# design.net
KiCad netlist of a schematic drawn in Altium Designer
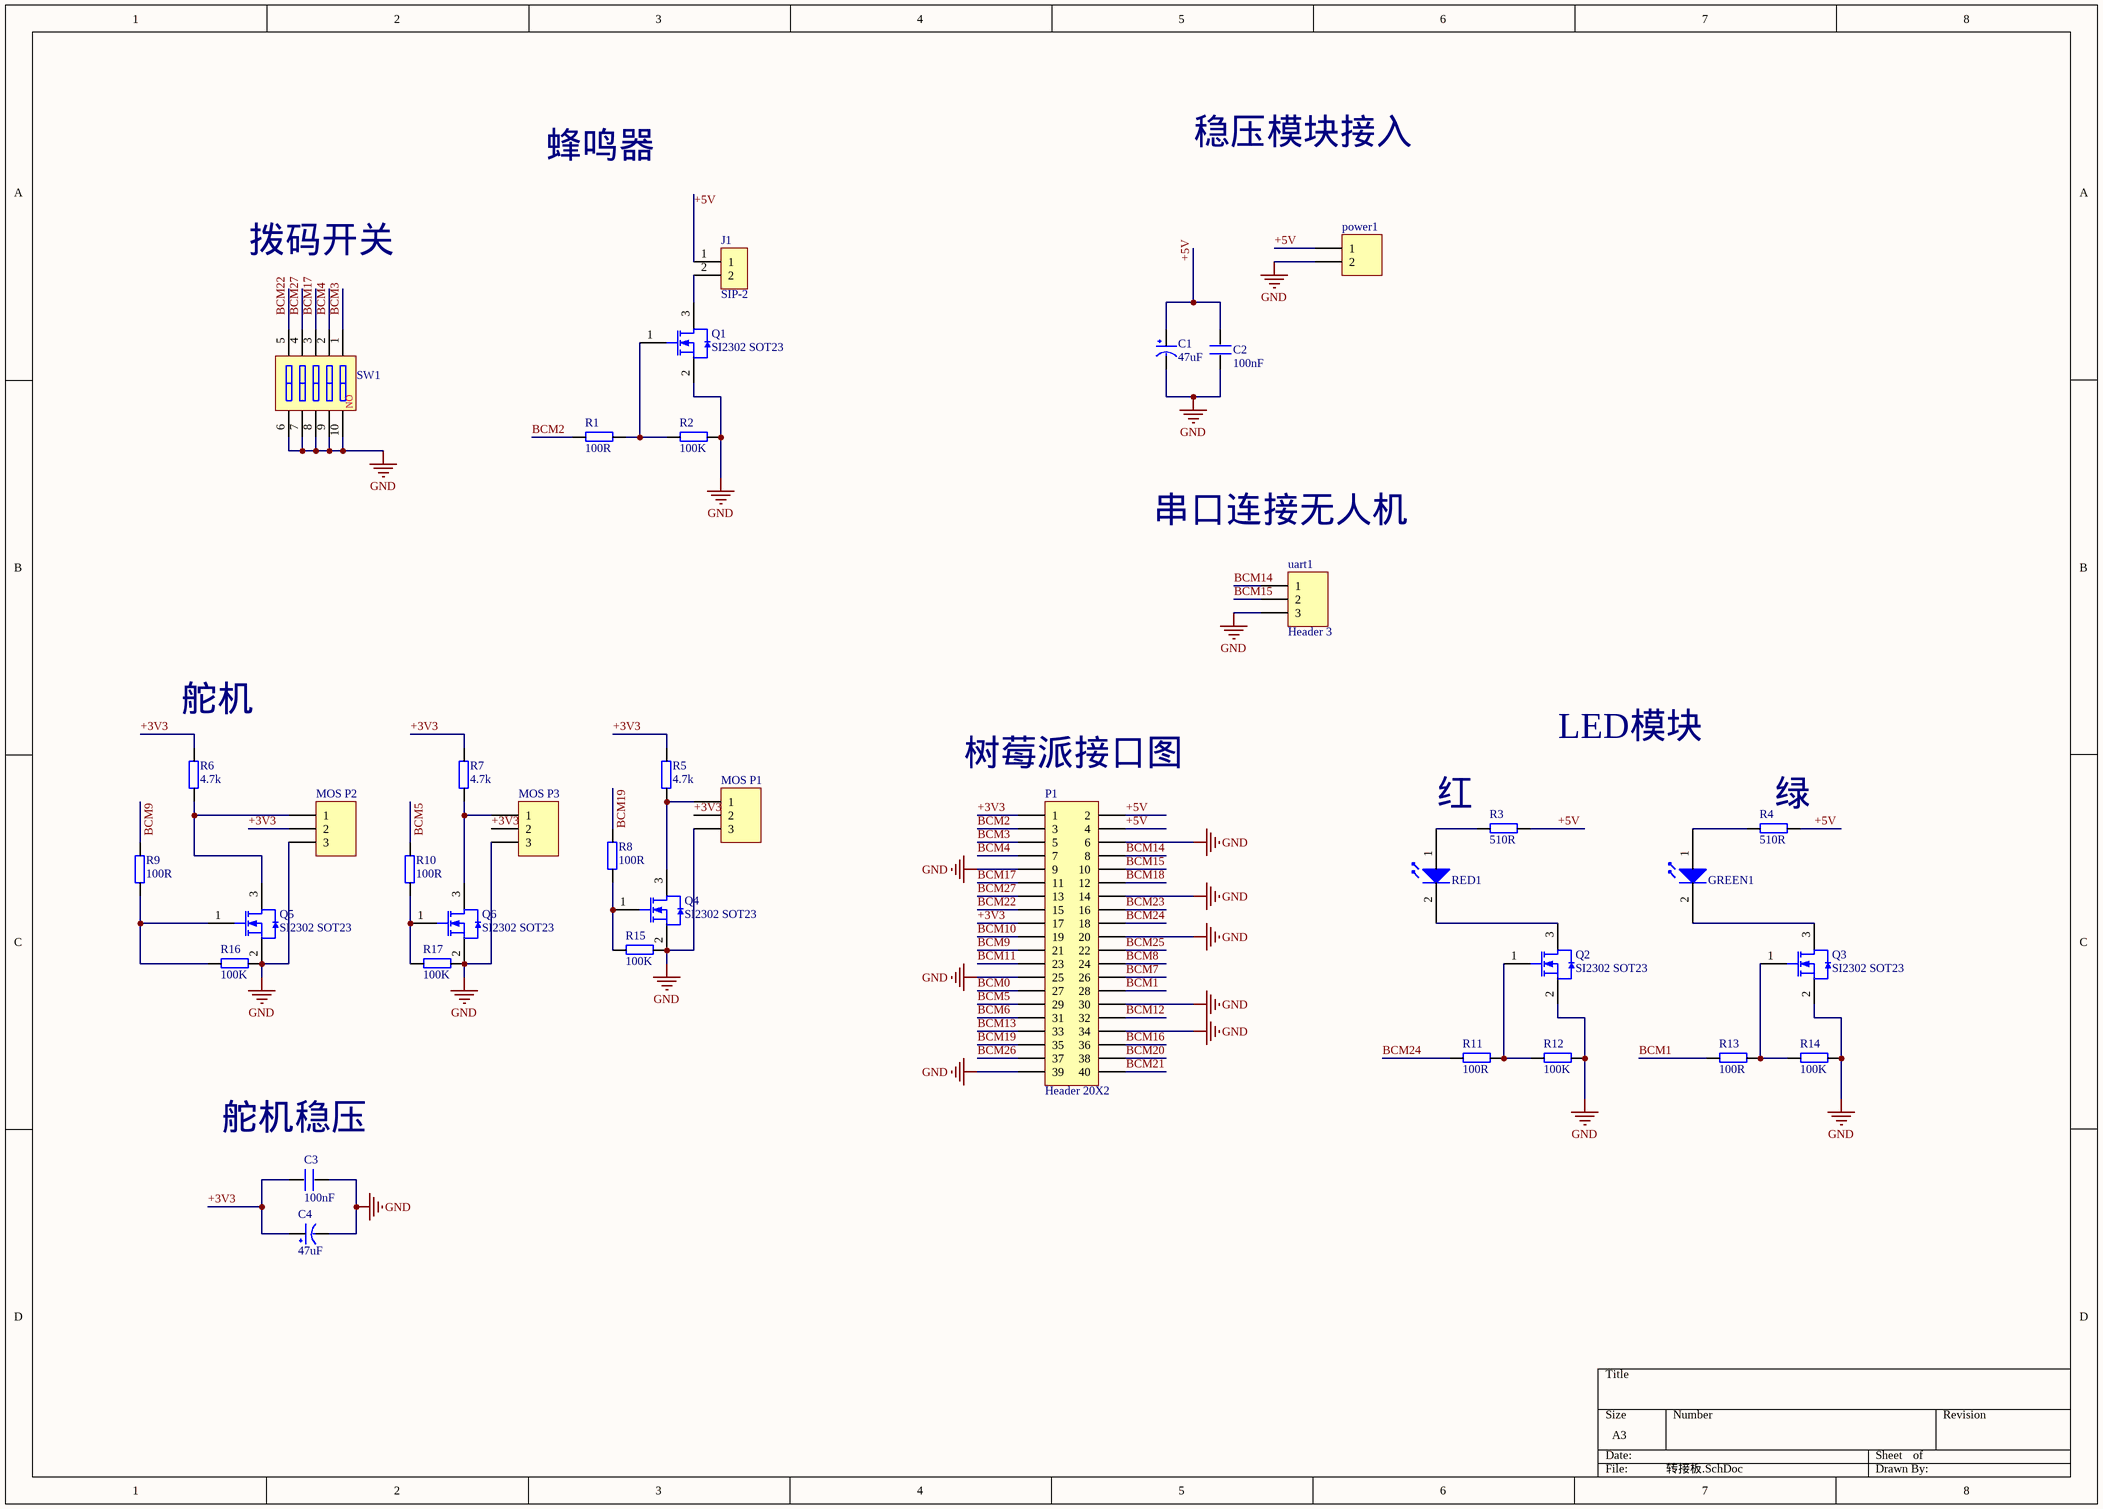
[diagram p0: 转接板.SchDoc]

(export (version "E")
  (design (tool "Eeschema 10.0.6"))
  (components
    (comp (ref "C1") (value "47uF") (footprint "3216") (libsource (lib "") (part "CAP_1")))
    (comp (ref "C2") (value "100nF") (footprint "0603P") (libsource (lib "SHUMVSchlib2.0") (part "C")))
    (comp (ref "C3") (value "100nF") (footprint "0603P") (libsource (lib "SHUMVSchlib2.0") (part "C")))
    (comp (ref "C4") (value "47uF") (footprint "3216") (libsource (lib "SHUMVSchlib2.0") (part "CAP")))
    (comp (ref "GREEN1") (value "LED?") (footprint "LED 5MM-G") (libsource (lib "元件库") (part "LED")))
    (comp (ref "J1") (value "SIP-2") (footprint "5.08接线端子2P") (libsource (lib "接插件") (part "SIP-2")))
    (comp (ref "MOS P1")
      (value "Header 3")
      (footprint "HDR1X3")
      (description "Header, 3-Pin")
      (fields (field (name "PUBLISHER") "Altium Limited"))
      (libsource (lib "Miscellaneous Connectors") (part "Header 3"))
    )
    (comp (ref "MOS P2")
      (value "Header 3")
      (footprint "HDR1X3")
      (description "Header, 3-Pin")
      (fields (field (name "PUBLISHER") "Altium Limited"))
      (libsource (lib "Miscellaneous Connectors") (part "Header 3"))
    )
    (comp (ref "MOS P3")
      (value "Header 3")
      (footprint "HDR1X3")
      (description "Header, 3-Pin")
      (fields (field (name "PUBLISHER") "Altium Limited"))
      (libsource (lib "Miscellaneous Connectors") (part "Header 3"))
    )
    (comp (ref "P1")
      (value "Header 20X2")
      (footprint "HDR2X20")
      (description "Header, 20-Pin, Dual row")
      (fields (field (name "PUBLISHER") "Altium Limited"))
      (libsource (lib "Miscellaneous Connectors") (part "Header 20X2"))
    )
    (comp (ref "power1")
      (value "Battery")
      (footprint "HDR1X2")
      (description "Header, 2-Pin")
      (fields (field (name "PUBLISHER") "Altium Limited"))
      (libsource (lib "SHUMVSchlib2.0") (part "Header 2"))
    )
    (comp (ref "Q1") (value "SI2302 SOT23") (footprint "SOT-23") (libsource (lib "CH340T") (part "NMOS")))
    (comp (ref "Q2") (value "SI2302 SOT23") (footprint "SOT-23") (libsource (lib "CH340T") (part "NMOS")))
    (comp (ref "Q3") (value "SI2302 SOT23") (footprint "SOT-23") (libsource (lib "CH340T") (part "NMOS")))
    (comp (ref "Q4") (value "SI2302 SOT23") (footprint "SOT-23") (libsource (lib "CH340T") (part "NMOS")))
    (comp (ref "Q5") (value "SI2302 SOT23") (footprint "SOT-23") (libsource (lib "CH340T") (part "NMOS")))
    (comp (ref "Q6") (value "SI2302 SOT23") (footprint "SOT-23") (libsource (lib "CH340T") (part "NMOS")))
    (comp (ref "R1") (value "100R") (footprint "0603P") (libsource (lib "SHUMVSchlib1") (part "R")))
    (comp (ref "R2") (value "100K") (footprint "0603P") (libsource (lib "SHUMVSchlib1") (part "R")))
    (comp (ref "R3") (value "510R") (footprint "0603P") (libsource (lib "SHUMVSchlib1") (part "R")))
    (comp (ref "R4") (value "510R") (footprint "0603P") (libsource (lib "SHUMVSchlib1") (part "R")))
    (comp (ref "R5") (value "4.7k") (footprint "0603P") (libsource (lib "SHUMVSchlib1") (part "R")))
    (comp (ref "R6") (value "4.7k") (footprint "0603P") (libsource (lib "SHUMVSchlib1") (part "R")))
    (comp (ref "R7") (value "4.7k") (footprint "0603P") (libsource (lib "SHUMVSchlib1") (part "R")))
    (comp (ref "R8") (value "100R") (footprint "0603P") (libsource (lib "SHUMVSchlib1") (part "R")))
    (comp (ref "R9") (value "100R") (footprint "0603P") (libsource (lib "SHUMVSchlib1") (part "R")))
    (comp (ref "R10") (value "100R") (footprint "0603P") (libsource (lib "SHUMVSchlib1") (part "R")))
    (comp (ref "R11") (value "100R") (footprint "0603P") (libsource (lib "SHUMVSchlib1") (part "R")))
    (comp (ref "R12") (value "100K") (footprint "0603P") (libsource (lib "SHUMVSchlib1") (part "R")))
    (comp (ref "R13") (value "100R") (footprint "0603P") (libsource (lib "SHUMVSchlib1") (part "R")))
    (comp (ref "R14") (value "100K") (footprint "0603P") (libsource (lib "SHUMVSchlib1") (part "R")))
    (comp (ref "R15") (value "100K") (footprint "0603P") (libsource (lib "SHUMVSchlib1") (part "R")))
    (comp (ref "R16") (value "100K") (footprint "0603P") (libsource (lib "SHUMVSchlib1") (part "R")))
    (comp (ref "R17") (value "100K") (footprint "0603P") (libsource (lib "SHUMVSchlib1") (part "R")))
    (comp (ref "RED1") (value "LED?") (footprint "LED 5MM-R") (libsource (lib "元件库") (part "LED")))
    (comp (ref "SW1") (value "5P") (footprint "拨码开关DIP-5P_G") (libsource (lib "开关") (part "拨码开关5P")))
    (comp (ref "uart1")
      (value "Header 3")
      (footprint "GH1.25-LS-3P")
      (description "Header, 3-Pin")
      (fields (field (name "PUBLISHER") "Altium Limited"))
      (libsource (lib "Miscellaneous Connectors") (part "Header 3"))
    )
  )
  (nets
    (net (code "1") (name "/+3V3") (class "Default")
      (node (ref "C3") (pin "2") (pintype "passive"))
      (node (ref "C4") (pin "1") (pinfunction "VCC_1") (pintype "passive"))
      (node (ref "MOS P1") (pin "2") (pinfunction "2_2") (pintype "passive"))
      (node (ref "MOS P2") (pin "2") (pinfunction "2_2") (pintype "passive"))
      (node (ref "MOS P3") (pin "2") (pinfunction "2_2") (pintype "passive"))
      (node (ref "P1") (pin "1") (pinfunction "1_1") (pintype "passive"))
      (node (ref "P1") (pin "17") (pinfunction "17_17") (pintype "passive"))
      (node (ref "R5") (pin "1") (pintype "passive"))
      (node (ref "R6") (pin "1") (pintype "passive"))
      (node (ref "R7") (pin "1") (pintype "passive"))
    )
    (net (code "2") (name "/+5V") (class "Default")
      (node (ref "C1") (pin "1") (pinfunction "VCC_1") (pintype "passive"))
      (node (ref "C2") (pin "2") (pintype "passive"))
      (node (ref "J1") (pin "1") (pinfunction "1_1") (pintype "passive"))
      (node (ref "P1") (pin "2") (pinfunction "2_2") (pintype "passive"))
      (node (ref "P1") (pin "4") (pinfunction "4_4") (pintype "passive"))
      (node (ref "R3") (pin "1") (pintype "passive"))
      (node (ref "R4") (pin "1") (pintype "passive"))
      (node (ref "power1") (pin "1") (pinfunction "1_1") (pintype "passive"))
    )
    (net (code "3") (name "/BCM0") (class "Default")
      (node (ref "P1") (pin "27") (pinfunction "27_27") (pintype "passive"))
    )
    (net (code "4") (name "/BCM1") (class "Default")
      (node (ref "P1") (pin "28") (pinfunction "28_28") (pintype "passive"))
      (node (ref "R13") (pin "2") (pintype "passive"))
    )
    (net (code "5") (name "/BCM2") (class "Default")
      (node (ref "P1") (pin "3") (pinfunction "3_3") (pintype "passive"))
      (node (ref "R1") (pin "2") (pintype "passive"))
    )
    (net (code "6") (name "/BCM3") (class "Default")
      (node (ref "P1") (pin "5") (pinfunction "5_5") (pintype "passive"))
      (node (ref "SW1") (pin "1") (pinfunction "1_1") (pintype "passive"))
    )
    (net (code "7") (name "/BCM4") (class "Default")
      (node (ref "P1") (pin "7") (pinfunction "7_7") (pintype "passive"))
      (node (ref "SW1") (pin "2") (pinfunction "2_2") (pintype "passive"))
    )
    (net (code "8") (name "/BCM5") (class "Default")
      (node (ref "P1") (pin "29") (pinfunction "29_29") (pintype "passive"))
      (node (ref "R10") (pin "1") (pintype "passive"))
    )
    (net (code "9") (name "/BCM6") (class "Default")
      (node (ref "P1") (pin "31") (pinfunction "31_31") (pintype "passive"))
    )
    (net (code "10") (name "/BCM7") (class "Default")
      (node (ref "P1") (pin "26") (pinfunction "26_26") (pintype "passive"))
    )
    (net (code "11") (name "/BCM8") (class "Default")
      (node (ref "P1") (pin "24") (pinfunction "24_24") (pintype "passive"))
    )
    (net (code "12") (name "/BCM9") (class "Default")
      (node (ref "P1") (pin "21") (pinfunction "21_21") (pintype "passive"))
      (node (ref "R9") (pin "1") (pintype "passive"))
    )
    (net (code "13") (name "/BCM10") (class "Default")
      (node (ref "P1") (pin "19") (pinfunction "19_19") (pintype "passive"))
    )
    (net (code "14") (name "/BCM11") (class "Default")
      (node (ref "P1") (pin "23") (pinfunction "23_23") (pintype "passive"))
    )
    (net (code "15") (name "/BCM12") (class "Default")
      (node (ref "P1") (pin "32") (pinfunction "32_32") (pintype "passive"))
    )
    (net (code "16") (name "/BCM13") (class "Default")
      (node (ref "P1") (pin "33") (pinfunction "33_33") (pintype "passive"))
    )
    (net (code "17") (name "/BCM14") (class "Default")
      (node (ref "P1") (pin "8") (pinfunction "8_8") (pintype "passive"))
      (node (ref "uart1") (pin "1") (pinfunction "1_1") (pintype "passive"))
    )
    (net (code "18") (name "/BCM15") (class "Default")
      (node (ref "P1") (pin "10") (pinfunction "10_10") (pintype "passive"))
      (node (ref "uart1") (pin "2") (pinfunction "2_2") (pintype "passive"))
    )
    (net (code "19") (name "/BCM16") (class "Default")
      (node (ref "P1") (pin "36") (pinfunction "36_36") (pintype "passive"))
    )
    (net (code "20") (name "/BCM17") (class "Default")
      (node (ref "P1") (pin "11") (pinfunction "11_11") (pintype "passive"))
      (node (ref "SW1") (pin "3") (pinfunction "3_3") (pintype "passive"))
    )
    (net (code "21") (name "/BCM18") (class "Default")
      (node (ref "P1") (pin "12") (pinfunction "12_12") (pintype "passive"))
    )
    (net (code "22") (name "/BCM19") (class "Default")
      (node (ref "P1") (pin "35") (pinfunction "35_35") (pintype "passive"))
      (node (ref "R8") (pin "1") (pintype "passive"))
    )
    (net (code "23") (name "/BCM20") (class "Default")
      (node (ref "P1") (pin "38") (pinfunction "38_38") (pintype "passive"))
    )
    (net (code "24") (name "/BCM21") (class "Default")
      (node (ref "P1") (pin "40") (pinfunction "40_40") (pintype "passive"))
    )
    (net (code "25") (name "/BCM22") (class "Default")
      (node (ref "P1") (pin "15") (pinfunction "15_15") (pintype "passive"))
      (node (ref "SW1") (pin "5") (pinfunction "5_5") (pintype "passive"))
    )
    (net (code "26") (name "/BCM23") (class "Default")
      (node (ref "P1") (pin "16") (pinfunction "16_16") (pintype "passive"))
    )
    (net (code "27") (name "/BCM24") (class "Default")
      (node (ref "P1") (pin "18") (pinfunction "18_18") (pintype "passive"))
      (node (ref "R11") (pin "2") (pintype "passive"))
    )
    (net (code "28") (name "/BCM25") (class "Default")
      (node (ref "P1") (pin "22") (pinfunction "22_22") (pintype "passive"))
    )
    (net (code "29") (name "/BCM26") (class "Default")
      (node (ref "P1") (pin "37") (pinfunction "37_37") (pintype "passive"))
    )
    (net (code "30") (name "/BCM27") (class "Default")
      (node (ref "P1") (pin "13") (pinfunction "13_13") (pintype "passive"))
      (node (ref "SW1") (pin "4") (pinfunction "4_4") (pintype "passive"))
    )
    (net (code "31") (name "GND") (class "Default")
      (node (ref "C1") (pin "2") (pinfunction "GND_2") (pintype "passive"))
      (node (ref "C2") (pin "1") (pintype "passive"))
      (node (ref "C3") (pin "1") (pintype "passive"))
      (node (ref "C4") (pin "2") (pinfunction "GND_2") (pintype "passive"))
      (node (ref "MOS P1") (pin "3") (pinfunction "3_3") (pintype "passive"))
      (node (ref "MOS P2") (pin "3") (pinfunction "3_3") (pintype "passive"))
      (node (ref "MOS P3") (pin "3") (pinfunction "3_3") (pintype "passive"))
      (node (ref "P1") (pin "14") (pinfunction "14_14") (pintype "passive"))
      (node (ref "P1") (pin "20") (pinfunction "20_20") (pintype "passive"))
      (node (ref "P1") (pin "25") (pinfunction "25_25") (pintype "passive"))
      (node (ref "P1") (pin "30") (pinfunction "30_30") (pintype "passive"))
      (node (ref "P1") (pin "34") (pinfunction "34_34") (pintype "passive"))
      (node (ref "P1") (pin "39") (pinfunction "39_39") (pintype "passive"))
      (node (ref "P1") (pin "6") (pinfunction "6_6") (pintype "passive"))
      (node (ref "P1") (pin "9") (pinfunction "9_9") (pintype "passive"))
      (node (ref "Q1") (pin "2") (pinfunction "S_2") (pintype "passive"))
      (node (ref "Q2") (pin "2") (pinfunction "S_2") (pintype "passive"))
      (node (ref "Q3") (pin "2") (pinfunction "S_2") (pintype "passive"))
      (node (ref "Q4") (pin "2") (pinfunction "S_2") (pintype "passive"))
      (node (ref "Q5") (pin "2") (pinfunction "S_2") (pintype "passive"))
      (node (ref "Q6") (pin "2") (pinfunction "S_2") (pintype "passive"))
      (node (ref "R12") (pin "1") (pintype "passive"))
      (node (ref "R14") (pin "1") (pintype "passive"))
      (node (ref "R15") (pin "1") (pintype "passive"))
      (node (ref "R16") (pin "1") (pintype "passive"))
      (node (ref "R17") (pin "1") (pintype "passive"))
      (node (ref "R2") (pin "1") (pintype "passive"))
      (node (ref "SW1") (pin "10") (pinfunction "10_10") (pintype "passive"))
      (node (ref "SW1") (pin "6") (pinfunction "6_6") (pintype "passive"))
      (node (ref "SW1") (pin "7") (pinfunction "7_7") (pintype "passive"))
      (node (ref "SW1") (pin "8") (pinfunction "8_8") (pintype "passive"))
      (node (ref "SW1") (pin "9") (pinfunction "9_9") (pintype "passive"))
      (node (ref "power1") (pin "2") (pinfunction "2_2") (pintype "passive"))
      (node (ref "uart1") (pin "3") (pinfunction "3_3") (pintype "passive"))
    )
    (net (code "32") (name "Net-(GREEN1-Pad1)") (class "Default")
      (node (ref "GREEN1") (pin "1") (pinfunction "1_1") (pintype "passive"))
      (node (ref "R4") (pin "2") (pintype "passive"))
    )
    (net (code "33") (name "Net-(Q1-D)") (class "Default")
      (node (ref "J1") (pin "2") (pinfunction "2_2") (pintype "passive"))
      (node (ref "Q1") (pin "3") (pinfunction "D_3") (pintype "passive"))
    )
    (net (code "34") (name "Net-(Q1-G)") (class "Default")
      (node (ref "Q1") (pin "1") (pinfunction "G_1") (pintype "passive"))
      (node (ref "R1") (pin "1") (pintype "passive"))
      (node (ref "R2") (pin "2") (pintype "passive"))
    )
    (net (code "35") (name "Net-(Q2-D)") (class "Default")
      (node (ref "Q2") (pin "3") (pinfunction "D_3") (pintype "passive"))
      (node (ref "RED1") (pin "2") (pinfunction "2_2") (pintype "passive"))
    )
    (net (code "36") (name "Net-(Q2-G)") (class "Default")
      (node (ref "Q2") (pin "1") (pinfunction "G_1") (pintype "passive"))
      (node (ref "R11") (pin "1") (pintype "passive"))
      (node (ref "R12") (pin "2") (pintype "passive"))
    )
    (net (code "37") (name "Net-(Q3-D)") (class "Default")
      (node (ref "GREEN1") (pin "2") (pinfunction "2_2") (pintype "passive"))
      (node (ref "Q3") (pin "3") (pinfunction "D_3") (pintype "passive"))
    )
    (net (code "38") (name "Net-(Q3-G)") (class "Default")
      (node (ref "Q3") (pin "1") (pinfunction "G_1") (pintype "passive"))
      (node (ref "R13") (pin "1") (pintype "passive"))
      (node (ref "R14") (pin "2") (pintype "passive"))
    )
    (net (code "39") (name "Net-(Q4-D)") (class "Default")
      (node (ref "MOS P1") (pin "1") (pinfunction "1_1") (pintype "passive"))
      (node (ref "Q4") (pin "3") (pinfunction "D_3") (pintype "passive"))
      (node (ref "R5") (pin "2") (pintype "passive"))
    )
    (net (code "40") (name "Net-(Q4-G)") (class "Default")
      (node (ref "Q4") (pin "1") (pinfunction "G_1") (pintype "passive"))
      (node (ref "R15") (pin "2") (pintype "passive"))
      (node (ref "R8") (pin "2") (pintype "passive"))
    )
    (net (code "41") (name "Net-(Q5-D)") (class "Default")
      (node (ref "MOS P2") (pin "1") (pinfunction "1_1") (pintype "passive"))
      (node (ref "Q5") (pin "3") (pinfunction "D_3") (pintype "passive"))
      (node (ref "R6") (pin "2") (pintype "passive"))
    )
    (net (code "42") (name "Net-(Q5-G)") (class "Default")
      (node (ref "Q5") (pin "1") (pinfunction "G_1") (pintype "passive"))
      (node (ref "R16") (pin "2") (pintype "passive"))
      (node (ref "R9") (pin "2") (pintype "passive"))
    )
    (net (code "43") (name "Net-(Q6-D)") (class "Default")
      (node (ref "MOS P3") (pin "1") (pinfunction "1_1") (pintype "passive"))
      (node (ref "Q6") (pin "3") (pinfunction "D_3") (pintype "passive"))
      (node (ref "R7") (pin "2") (pintype "passive"))
    )
    (net (code "44") (name "Net-(Q6-G)") (class "Default")
      (node (ref "Q6") (pin "1") (pinfunction "G_1") (pintype "passive"))
      (node (ref "R10") (pin "2") (pintype "passive"))
      (node (ref "R17") (pin "2") (pintype "passive"))
    )
    (net (code "45") (name "Net-(R3-Pad2)") (class "Default")
      (node (ref "R3") (pin "2") (pintype "passive"))
      (node (ref "RED1") (pin "1") (pinfunction "1_1") (pintype "passive"))
    )
  )
)
